# carte_ascenseur_v2.net
KiCad netlist of a schematic drawn in EAGLE
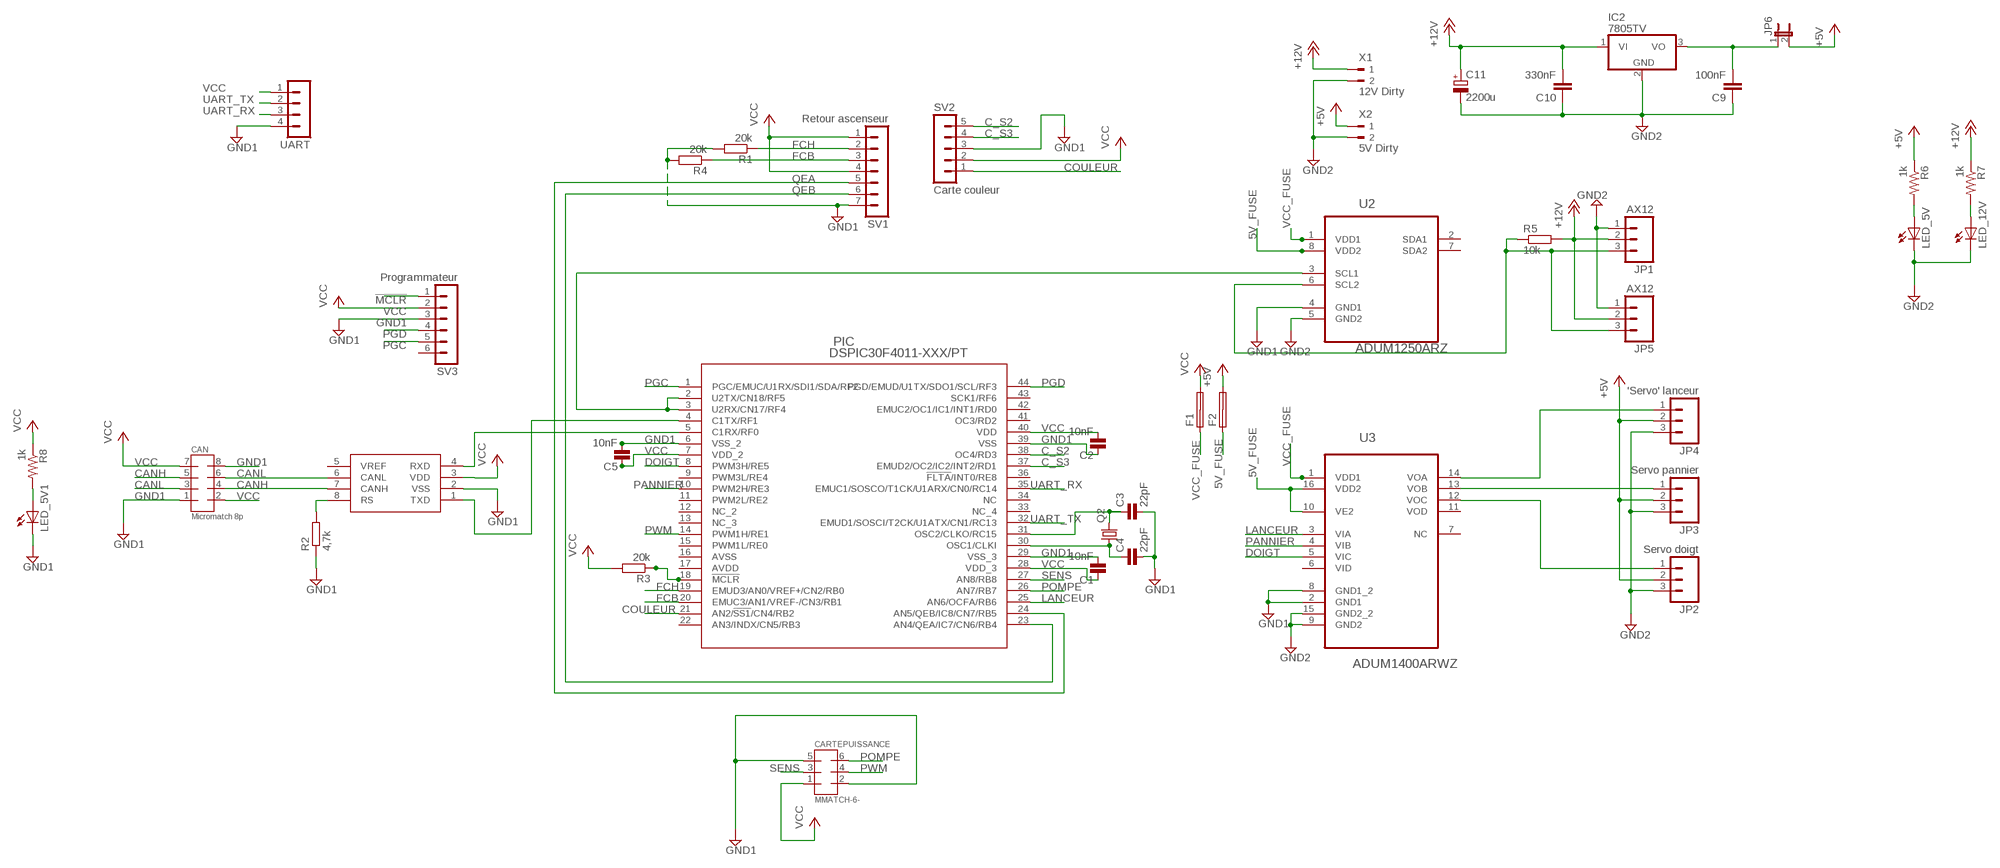
[diagram p0: schematic, sheet 1]

(export (version "E")
  (design (tool "Eeschema 10.0.6"))
  (components
    (comp (ref "C1")
      (value "10nF")
      (footprint "eagle-import:0805")
      (libsource (lib "eagle-import") (part "C0805"))
    )
    (comp (ref "C2")
      (value "10nF")
      (footprint "eagle-import:0805")
      (libsource (lib "eagle-import") (part "C0805"))
    )
    (comp (ref "C3")
      (value "22pF")
      (footprint "eagle-import:0805")
      (libsource (lib "eagle-import") (part "C0805"))
    )
    (comp (ref "C4")
      (value "22pF")
      (footprint "eagle-import:0805")
      (libsource (lib "eagle-import") (part "C0805"))
    )
    (comp (ref "C5")
      (value "10nF")
      (footprint "eagle-import:0805")
      (libsource (lib "eagle-import") (part "C0805"))
    )
    (comp (ref "C9")
      (value "100nF")
      (footprint "eagle-import:C0805")
      (libsource (lib "eagle-import") (part "C-EUC0805"))
    )
    (comp (ref "C10")
      (value "330nF")
      (footprint "eagle-import:C0805")
      (libsource (lib "eagle-import") (part "C-EUC0805"))
    )
    (comp (ref "C11")
      (value "2200u")
      (footprint "eagle-import:TT5D11")
      (libsource (lib "eagle-import") (part "CPOL-EUTT5D11"))
    )
    (comp (ref "CAN")
      (value "Micromatch 8p")
      (footprint "eagle-import:AMP-215079-8")
      (libsource (lib "eagle-import") (part "MMATCH-8-PTH"))
    )
    (comp (ref "CARTEPUISSANCE")
      (value "MMATCH-6-")
      (footprint "eagle-import:AMP-215079-6")
      (libsource (lib "eagle-import") (part "MMATCH-6-"))
    )
    (comp (ref "F1")
      (value "SHK20Q")
      (footprint "eagle-import:SHK20Q")
      (libsource (lib "eagle-import") (part "SHK20Q"))
    )
    (comp (ref "F2")
      (value "SHK20Q")
      (footprint "eagle-import:SHK20Q")
      (libsource (lib "eagle-import") (part "SHK20Q"))
    )
    (comp (ref "IC2")
      (value "7805TV")
      (footprint "eagle-import:TO220V")
      (libsource (lib "eagle-import") (part "78TV05"))
    )
    (comp (ref "JP1")
      (value "AX12")
      (footprint "eagle-import:MOLEX-1X3")
      (libsource (lib "eagle-import") (part "M03POLAR"))
    )
    (comp (ref "JP2")
      (value "Servo doigt")
      (footprint "eagle-import:1X03")
      (libsource (lib "eagle-import") (part "M03PTH"))
    )
    (comp (ref "JP3")
      (value "Servo pannier")
      (footprint "eagle-import:1X03")
      (libsource (lib "eagle-import") (part "M03PTH"))
    )
    (comp (ref "JP4")
      (value "'Servo' lanceur")
      (footprint "eagle-import:1X03")
      (libsource (lib "eagle-import") (part "M03PTH"))
    )
    (comp (ref "JP5")
      (value "AX12")
      (footprint "eagle-import:MOLEX-1X3")
      (libsource (lib "eagle-import") (part "M03POLAR"))
    )
    (comp (ref "JP6")
      (value "JP1E")
      (footprint "eagle-import:JP1")
      (libsource (lib "eagle-import") (part "JP1E"))
    )
    (comp (ref "LED_5V")
      (value "LEDCHIPLED_0805")
      (footprint "eagle-import:CHIPLED_0805")
      (libsource (lib "eagle-import") (part "LEDCHIPLED_0805"))
    )
    (comp (ref "LED_5V1")
      (value "LEDCHIPLED_0805")
      (footprint "eagle-import:CHIPLED_0805")
      (libsource (lib "eagle-import") (part "LEDCHIPLED_0805"))
    )
    (comp (ref "LED_12V")
      (value "LEDCHIPLED_0805")
      (footprint "eagle-import:CHIPLED_0805")
      (libsource (lib "eagle-import") (part "LEDCHIPLED_0805"))
    )
    (comp (ref "PIC")
      (value "DSPIC30F4011-XXX/PT")
      (footprint "eagle-import:TQFP44_MC")
      (libsource (lib "eagle-import") (part "DSPIC30F4011-XXX/PT"))
    )
    (comp (ref "Q2")
      (value "CRYSTALHC49S")
      (footprint "eagle-import:HC49_S")
      (libsource (lib "eagle-import") (part "CRYSTALHC49S"))
    )
    (comp (ref "R1")
      (value "20k")
      (footprint "eagle-import:M0805")
      (libsource (lib "eagle-import") (part "R-EU_M0805"))
    )
    (comp (ref "R2")
      (value "4,7k")
      (footprint "eagle-import:M0805")
      (libsource (lib "eagle-import") (part "R-EU_M0805"))
    )
    (comp (ref "R3")
      (value "20k")
      (footprint "eagle-import:M0805")
      (libsource (lib "eagle-import") (part "R-EU_M0805"))
    )
    (comp (ref "R4")
      (value "20k")
      (footprint "eagle-import:M0805")
      (libsource (lib "eagle-import") (part "R-EU_M0805"))
    )
    (comp (ref "R5")
      (value "10k")
      (footprint "eagle-import:M0805")
      (libsource (lib "eagle-import") (part "R-EU_M0805"))
    )
    (comp (ref "R6")
      (value "1k")
      (footprint "eagle-import:0805")
      (libsource (lib "eagle-import") (part "RESISTOR0805-RES"))
    )
    (comp (ref "R7")
      (value "1k")
      (footprint "eagle-import:0805")
      (libsource (lib "eagle-import") (part "RESISTOR0805-RES"))
    )
    (comp (ref "R8")
      (value "1k")
      (footprint "eagle-import:0805")
      (libsource (lib "eagle-import") (part "RESISTOR0805-RES"))
    )
    (comp (ref "SV1")
      (value "Retour ascenseur")
      (footprint "eagle-import:MA07-1")
      (libsource (lib "eagle-import") (part "MA07-1"))
    )
    (comp (ref "SV2")
      (value "Carte couleur")
      (footprint "eagle-import:MA05-1")
      (libsource (lib "eagle-import") (part "MA05-1"))
    )
    (comp (ref "SV3")
      (value "Programmateur")
      (footprint "eagle-import:MA06-1")
      (libsource (lib "eagle-import") (part "MA06-1"))
    )
    (comp (ref "U1")
      (value "MCP2551")
      (footprint "eagle-import:SO08")
      (libsource (lib "eagle-import") (part "MCP2551"))
    )
    (comp (ref "U2")
      (value "ADUM1250ARZ")
      (footprint "eagle-import:SOIC127P600X175-8N")
      (libsource (lib "eagle-import") (part "ADUM1250ARZ"))
    )
    (comp (ref "U3")
      (value "ADUM1400ARWZ")
      (footprint "eagle-import:SOIC127P1032X265-16N")
      (libsource (lib "eagle-import") (part "ADUM1400ARWZ"))
    )
    (comp (ref "UART")
      (value "MA04-1")
      (footprint "eagle-import:MA04-1")
      (libsource (lib "eagle-import") (part "MA04-1"))
    )
    (comp (ref "X1")
      (value "12V Dirty")
      (footprint "eagle-import:90-2")
      (libsource (lib "eagle-import") (part "90-2"))
    )
    (comp (ref "X2")
      (value "5V Dirty")
      (footprint "eagle-import:90-2")
      (fields (field (name "OC_FARNELL") "unknown") (field (name "OC_NEWARK") "unknown"))
      (libsource (lib "eagle-import") (part "90-2"))
    )
  )
  (nets
    (net (code "1") (name "+5V") (class "Default")
      (node (ref "F2") (pin "2A") (pinfunction "2A_2A") (pintype "passive"))
      (node (ref "JP2") (pin "2") (pinfunction "2_2") (pintype "passive"))
      (node (ref "JP3") (pin "2") (pinfunction "2_2") (pintype "passive"))
      (node (ref "JP4") (pin "2") (pinfunction "2_2") (pintype "passive"))
      (node (ref "JP6") (pin "2") (pinfunction "2_2") (pintype "passive"))
      (node (ref "R6") (pin "1") (pinfunction "1_1") (pintype "passive"))
      (node (ref "X2") (pin "1") (pinfunction "1_1") (pintype "passive"))
    )
    (net (code "2") (name "+12V") (class "Default")
      (node (ref "C10") (pin "2") (pinfunction "2_2") (pintype "passive"))
      (node (ref "C11") (pin "+") (pinfunction "+_+") (pintype "passive"))
      (node (ref "IC2") (pin "1") (pinfunction "VI_1") (pintype "input"))
      (node (ref "JP1") (pin "2") (pinfunction "2_2") (pintype "passive"))
      (node (ref "JP5") (pin "2") (pinfunction "2_2") (pintype "passive"))
      (node (ref "R5") (pin "2") (pinfunction "2_2") (pintype "passive"))
      (node (ref "R7") (pin "1") (pinfunction "1_1") (pintype "passive"))
      (node (ref "X1") (pin "1") (pinfunction "1_1") (pintype "passive"))
    )
    (net (code "3") (name "/5V_FUSE") (class "Default")
      (node (ref "F2") (pin "1A") (pinfunction "1A_1A") (pintype "passive"))
      (node (ref "U2") (pin "8") (pinfunction "VDD2_8") (pintype "power_in"))
      (node (ref "U3") (pin "10") (pinfunction "VE2_10") (pintype "input"))
      (node (ref "U3") (pin "16") (pinfunction "VDD2_16") (pintype "power_in"))
    )
    (net (code "4") (name "/CANH") (class "Default")
      (node (ref "CAN") (pin "4") (pinfunction "4_4") (pintype "bidirectional"))
      (node (ref "CAN") (pin "5") (pinfunction "5_5") (pintype "bidirectional"))
      (node (ref "U1") (pin "7") (pinfunction "CANH_7") (pintype "bidirectional"))
    )
    (net (code "5") (name "/CANL") (class "Default")
      (node (ref "CAN") (pin "3") (pinfunction "3_3") (pintype "bidirectional"))
      (node (ref "CAN") (pin "6") (pinfunction "6_6") (pintype "bidirectional"))
      (node (ref "U1") (pin "6") (pinfunction "CANL_6") (pintype "bidirectional"))
    )
    (net (code "6") (name "/COULEUR") (class "Default")
      (node (ref "PIC") (pin "21") (pinfunction "AN2/~{SS1}/CN4/RB2_21") (pintype "passive"))
      (node (ref "SV2") (pin "1") (pinfunction "1_1") (pintype "passive"))
    )
    (net (code "7") (name "/C_S2") (class "Default")
      (node (ref "PIC") (pin "38") (pinfunction "OC4/RD3_38") (pintype "passive"))
      (node (ref "SV2") (pin "5") (pinfunction "5_5") (pintype "passive"))
    )
    (net (code "8") (name "/C_S3") (class "Default")
      (node (ref "PIC") (pin "37") (pinfunction "EMUD2/OC2/IC2/INT2/RD1_37") (pintype "passive"))
      (node (ref "SV2") (pin "4") (pinfunction "4_4") (pintype "passive"))
    )
    (net (code "9") (name "/DOIGT") (class "Default")
      (node (ref "PIC") (pin "8") (pinfunction "PWM3H/RE5_8") (pintype "passive"))
      (node (ref "U3") (pin "5") (pinfunction "VIC_5") (pintype "input"))
    )
    (net (code "10") (name "/FCB") (class "Default")
      (node (ref "PIC") (pin "20") (pinfunction "EMUC3/AN1/VREF-/CN3/RB1_20") (pintype "passive"))
      (node (ref "R4") (pin "1") (pinfunction "1_1") (pintype "passive"))
      (node (ref "SV1") (pin "3") (pinfunction "3_3") (pintype "passive"))
    )
    (net (code "11") (name "/FCH") (class "Default")
      (node (ref "PIC") (pin "19") (pinfunction "EMUD3/AN0/VREF+/CN2/RB0_19") (pintype "passive"))
      (node (ref "R1") (pin "1") (pinfunction "1_1") (pintype "passive"))
      (node (ref "SV1") (pin "2") (pinfunction "2_2") (pintype "passive"))
    )
    (net (code "12") (name "/LANCEUR") (class "Default")
      (node (ref "PIC") (pin "25") (pinfunction "AN6/OCFA/RB6_25") (pintype "passive"))
      (node (ref "U3") (pin "3") (pinfunction "VIA_3") (pintype "input"))
    )
    (net (code "13") (name "/PANNIER") (class "Default")
      (node (ref "PIC") (pin "10") (pinfunction "PWM2H/RE3_10") (pintype "passive"))
      (node (ref "U3") (pin "4") (pinfunction "VIB_4") (pintype "input"))
    )
    (net (code "14") (name "/PGC") (class "Default")
      (node (ref "PIC") (pin "1") (pinfunction "PGC/EMUC/U1RX/SDI1/SDA/RF2_1") (pintype "passive"))
      (node (ref "SV3") (pin "5") (pinfunction "5_5") (pintype "passive"))
    )
    (net (code "15") (name "/PGD") (class "Default")
      (node (ref "PIC") (pin "44") (pinfunction "PGD/EMUD/U1TX/SDO1/SCL/RF3_44") (pintype "passive"))
      (node (ref "SV3") (pin "4") (pinfunction "4_4") (pintype "passive"))
    )
    (net (code "16") (name "/POMPE") (class "Default")
      (node (ref "CARTEPUISSANCE") (pin "6") (pinfunction "8_6") (pintype "bidirectional"))
      (node (ref "PIC") (pin "26") (pinfunction "AN7/RB7_26") (pintype "passive"))
    )
    (net (code "17") (name "/PWM") (class "Default")
      (node (ref "CARTEPUISSANCE") (pin "4") (pinfunction "6_4") (pintype "bidirectional"))
      (node (ref "PIC") (pin "14") (pinfunction "PWM1H/RE1_14") (pintype "passive"))
    )
    (net (code "18") (name "/QEA") (class "Default")
      (node (ref "PIC") (pin "24") (pinfunction "AN5/QEB/IC8/CN7/RB5_24") (pintype "passive"))
      (node (ref "SV1") (pin "5") (pinfunction "5_5") (pintype "passive"))
    )
    (net (code "19") (name "/QEB") (class "Default")
      (node (ref "PIC") (pin "23") (pinfunction "AN4/QEA/IC7/CN6/RB4_23") (pintype "passive"))
      (node (ref "SV1") (pin "6") (pinfunction "6_6") (pintype "passive"))
    )
    (net (code "20") (name "/SENS") (class "Default")
      (node (ref "CARTEPUISSANCE") (pin "3") (pinfunction "5_3") (pintype "bidirectional"))
      (node (ref "PIC") (pin "27") (pinfunction "AN8/RB8_27") (pintype "passive"))
    )
    (net (code "21") (name "/UART_RX") (class "Default")
      (node (ref "PIC") (pin "35") (pinfunction "EMUC1/SOSCO/T1CK/U1ARX/CN0/RC14_35") (pintype "passive"))
      (node (ref "UART") (pin "3") (pinfunction "3_3") (pintype "passive"))
    )
    (net (code "22") (name "/UART_TX") (class "Default")
      (node (ref "PIC") (pin "32") (pinfunction "EMUD1/SOSCI/T2CK/U1ATX/CN1/RC13_32") (pintype "passive"))
      (node (ref "UART") (pin "2") (pinfunction "2_2") (pintype "passive"))
    )
    (net (code "23") (name "/VCC_FUSE") (class "Default")
      (node (ref "F1") (pin "1A") (pinfunction "1A_1A") (pintype "passive"))
      (node (ref "U2") (pin "1") (pinfunction "VDD1_1") (pintype "power_in"))
      (node (ref "U3") (pin "1") (pinfunction "VDD1_1") (pintype "power_in"))
    )
    (net (code "24") (name "/~{MCLR}") (class "Default")
      (node (ref "PIC") (pin "18") (pinfunction "~{MCLR}_18") (pintype "passive"))
      (node (ref "R3") (pin "1") (pinfunction "1_1") (pintype "passive"))
      (node (ref "SV3") (pin "1") (pinfunction "1_1") (pintype "passive"))
    )
    (net (code "25") (name "GND1") (class "Default")
      (node (ref "C1") (pin "2") (pinfunction "P$2_2") (pintype "passive"))
      (node (ref "C2") (pin "1") (pinfunction "P$1_1") (pintype "passive"))
      (node (ref "C3") (pin "2") (pinfunction "P$2_2") (pintype "passive"))
      (node (ref "C4") (pin "2") (pinfunction "P$2_2") (pintype "passive"))
      (node (ref "C5") (pin "2") (pinfunction "P$2_2") (pintype "passive"))
      (node (ref "CAN") (pin "1") (pinfunction "1_1") (pintype "bidirectional"))
      (node (ref "CAN") (pin "8") (pinfunction "8_8") (pintype "bidirectional"))
      (node (ref "CARTEPUISSANCE") (pin "2") (pinfunction "4_2") (pintype "bidirectional"))
      (node (ref "CARTEPUISSANCE") (pin "5") (pinfunction "7_5") (pintype "bidirectional"))
      (node (ref "LED_5V1") (pin "C") (pinfunction "C_C") (pintype "passive"))
      (node (ref "PIC") (pin "29") (pinfunction "VSS_3_29") (pintype "passive"))
      (node (ref "PIC") (pin "39") (pinfunction "VSS_39") (pintype "passive"))
      (node (ref "PIC") (pin "6") (pinfunction "VSS_2_6") (pintype "passive"))
      (node (ref "R1") (pin "2") (pinfunction "2_2") (pintype "passive"))
      (node (ref "R2") (pin "1") (pinfunction "1_1") (pintype "passive"))
      (node (ref "R4") (pin "2") (pinfunction "2_2") (pintype "passive"))
      (node (ref "SV1") (pin "7") (pinfunction "7_7") (pintype "passive"))
      (node (ref "SV2") (pin "3") (pinfunction "3_3") (pintype "passive"))
      (node (ref "SV3") (pin "3") (pinfunction "3_3") (pintype "passive"))
      (node (ref "U1") (pin "2") (pinfunction "VSS_2") (pintype "bidirectional"))
      (node (ref "U2") (pin "4") (pinfunction "GND1_4") (pintype "passive"))
      (node (ref "U3") (pin "2") (pinfunction "GND1_2") (pintype "passive"))
      (node (ref "U3") (pin "8") (pinfunction "GND1_2_8") (pintype "passive"))
      (node (ref "UART") (pin "4") (pinfunction "4_4") (pintype "passive"))
    )
    (net (code "26") (name "GND2") (class "Default")
      (node (ref "C10") (pin "1") (pinfunction "1_1") (pintype "passive"))
      (node (ref "C11") (pin "-") (pinfunction "-_-") (pintype "passive"))
      (node (ref "C9") (pin "1") (pinfunction "1_1") (pintype "passive"))
      (node (ref "IC2") (pin "2") (pinfunction "GND_2") (pintype "passive"))
      (node (ref "JP1") (pin "1") (pinfunction "1_1") (pintype "passive"))
      (node (ref "JP2") (pin "3") (pinfunction "3_3") (pintype "passive"))
      (node (ref "JP3") (pin "3") (pinfunction "3_3") (pintype "passive"))
      (node (ref "JP4") (pin "3") (pinfunction "3_3") (pintype "passive"))
      (node (ref "JP5") (pin "1") (pinfunction "1_1") (pintype "passive"))
      (node (ref "LED_12V") (pin "C") (pinfunction "C_C") (pintype "passive"))
      (node (ref "LED_5V") (pin "C") (pinfunction "C_C") (pintype "passive"))
      (node (ref "U2") (pin "5") (pinfunction "GND2_5") (pintype "passive"))
      (node (ref "U3") (pin "15") (pinfunction "GND2_2_15") (pintype "passive"))
      (node (ref "U3") (pin "9") (pinfunction "GND2_9") (pintype "passive"))
      (node (ref "X1") (pin "2") (pinfunction "2_2") (pintype "passive"))
      (node (ref "X2") (pin "2") (pinfunction "2_2") (pintype "passive"))
    )
    (net (code "27") (name "Net-(C3-P$1)") (class "Default")
      (node (ref "C3") (pin "1") (pinfunction "P$1_1") (pintype "passive"))
      (node (ref "PIC") (pin "31") (pinfunction "OSC2/CLKO/RC15_31") (pintype "passive"))
      (node (ref "Q2") (pin "2") (pinfunction "2_2") (pintype "passive"))
    )
    (net (code "28") (name "Net-(C4-P$1)") (class "Default")
      (node (ref "C4") (pin "1") (pinfunction "P$1_1") (pintype "passive"))
      (node (ref "PIC") (pin "30") (pinfunction "OSC1/CLKI_30") (pintype "passive"))
      (node (ref "Q2") (pin "1") (pinfunction "1_1") (pintype "passive"))
    )
    (net (code "29") (name "Net-(IC2-VO)") (class "Default")
      (node (ref "C9") (pin "2") (pinfunction "2_2") (pintype "passive"))
      (node (ref "IC2") (pin "3") (pinfunction "VO_3") (pintype "passive"))
      (node (ref "JP6") (pin "1") (pinfunction "1_1") (pintype "passive"))
    )
    (net (code "30") (name "Net-(LED_5V-PadA)") (class "Default")
      (node (ref "LED_5V") (pin "A") (pinfunction "A_A") (pintype "passive"))
      (node (ref "R6") (pin "2") (pinfunction "2_2") (pintype "passive"))
    )
    (net (code "31") (name "Net-(LED_5V1-PadA)") (class "Default")
      (node (ref "LED_5V1") (pin "A") (pinfunction "A_A") (pintype "passive"))
      (node (ref "R8") (pin "2") (pinfunction "2_2") (pintype "passive"))
    )
    (net (code "32") (name "Net-(LED_12V-PadA)") (class "Default")
      (node (ref "LED_12V") (pin "A") (pinfunction "A_A") (pintype "passive"))
      (node (ref "R7") (pin "2") (pinfunction "2_2") (pintype "passive"))
    )
    (net (code "33") (name "Net-(PIC-C1RX{slash}RF0)") (class "Default")
      (node (ref "PIC") (pin "5") (pinfunction "C1RX/RF0_5") (pintype "passive"))
      (node (ref "U1") (pin "4") (pinfunction "RXD_4") (pintype "bidirectional"))
    )
    (net (code "34") (name "Net-(PIC-C1TX{slash}RF1)") (class "Default")
      (node (ref "PIC") (pin "4") (pinfunction "C1TX/RF1_4") (pintype "passive"))
      (node (ref "U1") (pin "1") (pinfunction "TXD_1") (pintype "bidirectional"))
    )
    (net (code "35") (name "Net-(PIC-U2RX{slash}CN17{slash}RF4)") (class "Default")
      (node (ref "PIC") (pin "2") (pinfunction "U2TX/CN18/RF5_2") (pintype "passive"))
      (node (ref "PIC") (pin "3") (pinfunction "U2RX/CN17/RF4_3") (pintype "passive"))
      (node (ref "U2") (pin "3") (pinfunction "SCL1_3") (pintype "input"))
    )
    (net (code "36") (name "Net-(U1-RS)") (class "Default")
      (node (ref "R2") (pin "2") (pinfunction "2_2") (pintype "passive"))
      (node (ref "U1") (pin "8") (pinfunction "RS_8") (pintype "bidirectional"))
    )
    (net (code "37") (name "Net-(U2-SCL2)") (class "Default")
      (node (ref "JP1") (pin "3") (pinfunction "3_3") (pintype "passive"))
      (node (ref "JP5") (pin "3") (pinfunction "3_3") (pintype "passive"))
      (node (ref "R5") (pin "1") (pinfunction "1_1") (pintype "passive"))
      (node (ref "U2") (pin "6") (pinfunction "SCL2_6") (pintype "input"))
    )
    (net (code "38") (name "Net-(U3-VOA)") (class "Default")
      (node (ref "JP4") (pin "1") (pinfunction "1_1") (pintype "passive"))
      (node (ref "U3") (pin "14") (pinfunction "VOA_14") (pintype "output"))
    )
    (net (code "39") (name "Net-(U3-VOB)") (class "Default")
      (node (ref "JP3") (pin "1") (pinfunction "1_1") (pintype "passive"))
      (node (ref "U3") (pin "13") (pinfunction "VOB_13") (pintype "output"))
    )
    (net (code "40") (name "Net-(U3-VOC)") (class "Default")
      (node (ref "JP2") (pin "1") (pinfunction "1_1") (pintype "passive"))
      (node (ref "U3") (pin "12") (pinfunction "VOC_12") (pintype "output"))
    )
    (net (code "41") (name "VCC") (class "Default")
      (node (ref "C1") (pin "1") (pinfunction "P$1_1") (pintype "passive"))
      (node (ref "C2") (pin "2") (pinfunction "P$2_2") (pintype "passive"))
      (node (ref "C5") (pin "1") (pinfunction "P$1_1") (pintype "passive"))
      (node (ref "CAN") (pin "2") (pinfunction "2_2") (pintype "bidirectional"))
      (node (ref "CAN") (pin "7") (pinfunction "7_7") (pintype "bidirectional"))
      (node (ref "CARTEPUISSANCE") (pin "1") (pinfunction "3_1") (pintype "bidirectional"))
      (node (ref "F1") (pin "2A") (pinfunction "2A_2A") (pintype "passive"))
      (node (ref "PIC") (pin "28") (pinfunction "VDD_3_28") (pintype "passive"))
      (node (ref "PIC") (pin "40") (pinfunction "VDD_40") (pintype "passive"))
      (node (ref "PIC") (pin "7") (pinfunction "VDD_2_7") (pintype "passive"))
      (node (ref "R3") (pin "2") (pinfunction "2_2") (pintype "passive"))
      (node (ref "R8") (pin "1") (pinfunction "1_1") (pintype "passive"))
      (node (ref "SV1") (pin "1") (pinfunction "1_1") (pintype "passive"))
      (node (ref "SV1") (pin "4") (pinfunction "4_4") (pintype "passive"))
      (node (ref "SV2") (pin "2") (pinfunction "2_2") (pintype "passive"))
      (node (ref "SV3") (pin "2") (pinfunction "2_2") (pintype "passive"))
      (node (ref "U1") (pin "3") (pinfunction "VDD_3") (pintype "bidirectional"))
      (node (ref "UART") (pin "1") (pinfunction "1_1") (pintype "passive"))
    )
    (net (code "42") (name "unconnected-(F1-Pad1B)") (class "Default")
      (node (ref "F1") (pin "1B") (pinfunction "1B_1B") (pintype "passive"))
    )
    (net (code "43") (name "unconnected-(F1-Pad2B)") (class "Default")
      (node (ref "F1") (pin "2B") (pinfunction "2B_2B") (pintype "passive"))
    )
    (net (code "44") (name "unconnected-(F2-Pad1B)") (class "Default")
      (node (ref "F2") (pin "1B") (pinfunction "1B_1B") (pintype "passive"))
    )
    (net (code "45") (name "unconnected-(F2-Pad2B)") (class "Default")
      (node (ref "F2") (pin "2B") (pinfunction "2B_2B") (pintype "passive"))
    )
    (net (code "46") (name "unconnected-(PIC-AN3{slash}INDX{slash}CN5{slash}RB3-Pad22)") (class "Default")
      (node (ref "PIC") (pin "22") (pinfunction "AN3/INDX/CN5/RB3_22") (pintype "passive"))
    )
    (net (code "47") (name "unconnected-(PIC-AVDD-Pad17)") (class "Default")
      (node (ref "PIC") (pin "17") (pinfunction "AVDD_17") (pintype "passive"))
    )
    (net (code "48") (name "unconnected-(PIC-AVSS-Pad16)") (class "Default")
      (node (ref "PIC") (pin "16") (pinfunction "AVSS_16") (pintype "passive"))
    )
    (net (code "49") (name "unconnected-(PIC-EMUC2{slash}OC1{slash}IC1{slash}INT1{slash}RD0-Pad42)") (class "Default")
      (node (ref "PIC") (pin "42") (pinfunction "EMUC2/OC1/IC1/INT1/RD0_42") (pintype "passive"))
    )
    (net (code "50") (name "unconnected-(PIC-NC-Pad34)") (class "Default")
      (node (ref "PIC") (pin "34") (pinfunction "NC_34") (pintype "passive"))
    )
    (net (code "51") (name "unconnected-(PIC-NC_2-Pad12)") (class "Default")
      (node (ref "PIC") (pin "12") (pinfunction "NC_2_12") (pintype "passive"))
    )
    (net (code "52") (name "unconnected-(PIC-NC_3-Pad13)") (class "Default")
      (node (ref "PIC") (pin "13") (pinfunction "NC_3_13") (pintype "passive"))
    )
    (net (code "53") (name "unconnected-(PIC-NC_4-Pad33)") (class "Default")
      (node (ref "PIC") (pin "33") (pinfunction "NC_4_33") (pintype "passive"))
    )
    (net (code "54") (name "unconnected-(PIC-OC3{slash}RD2-Pad41)") (class "Default")
      (node (ref "PIC") (pin "41") (pinfunction "OC3/RD2_41") (pintype "passive"))
    )
    (net (code "55") (name "unconnected-(PIC-PWM1L{slash}RE0-Pad15)") (class "Default")
      (node (ref "PIC") (pin "15") (pinfunction "PWM1L/RE0_15") (pintype "passive"))
    )
    (net (code "56") (name "unconnected-(PIC-PWM2L{slash}RE2-Pad11)") (class "Default")
      (node (ref "PIC") (pin "11") (pinfunction "PWM2L/RE2_11") (pintype "passive"))
    )
    (net (code "57") (name "unconnected-(PIC-PWM3L{slash}RE4-Pad9)") (class "Default")
      (node (ref "PIC") (pin "9") (pinfunction "PWM3L/RE4_9") (pintype "passive"))
    )
    (net (code "58") (name "unconnected-(PIC-SCK1{slash}RF6-Pad43)") (class "Default")
      (node (ref "PIC") (pin "43") (pinfunction "SCK1/RF6_43") (pintype "passive"))
    )
    (net (code "59") (name "unconnected-(PIC-~{FLTA}{slash}INT0{slash}RE8-Pad36)") (class "Default")
      (node (ref "PIC") (pin "36") (pinfunction "~{FLTA}/INT0/RE8_36") (pintype "passive"))
    )
    (net (code "60") (name "unconnected-(SV3-Pad6)") (class "Default")
      (node (ref "SV3") (pin "6") (pinfunction "6_6") (pintype "passive"))
    )
    (net (code "61") (name "unconnected-(U1-VREF-Pad5)") (class "Default")
      (node (ref "U1") (pin "5") (pinfunction "VREF_5") (pintype "bidirectional"))
    )
    (net (code "62") (name "unconnected-(U2-SDA1-Pad2)") (class "Default")
      (node (ref "U2") (pin "2") (pinfunction "SDA1_2") (pintype "bidirectional"))
    )
    (net (code "63") (name "unconnected-(U2-SDA2-Pad7)") (class "Default")
      (node (ref "U2") (pin "7") (pinfunction "SDA2_7") (pintype "bidirectional"))
    )
    (net (code "64") (name "unconnected-(U3-NC-Pad7)") (class "Default")
      (node (ref "U3") (pin "7") (pinfunction "NC_7") (pintype "no_connect"))
    )
    (net (code "65") (name "unconnected-(U3-VID-Pad6)") (class "Default")
      (node (ref "U3") (pin "6") (pinfunction "VID_6") (pintype "input"))
    )
    (net (code "66") (name "unconnected-(U3-VOD-Pad11)") (class "Default")
      (node (ref "U3") (pin "11") (pinfunction "VOD_11") (pintype "output"))
    )
  )
)
